# OSO-MISC-20-023_Trinket_SWD_Adapter.net
KiCad netlist of a schematic drawn in EAGLE
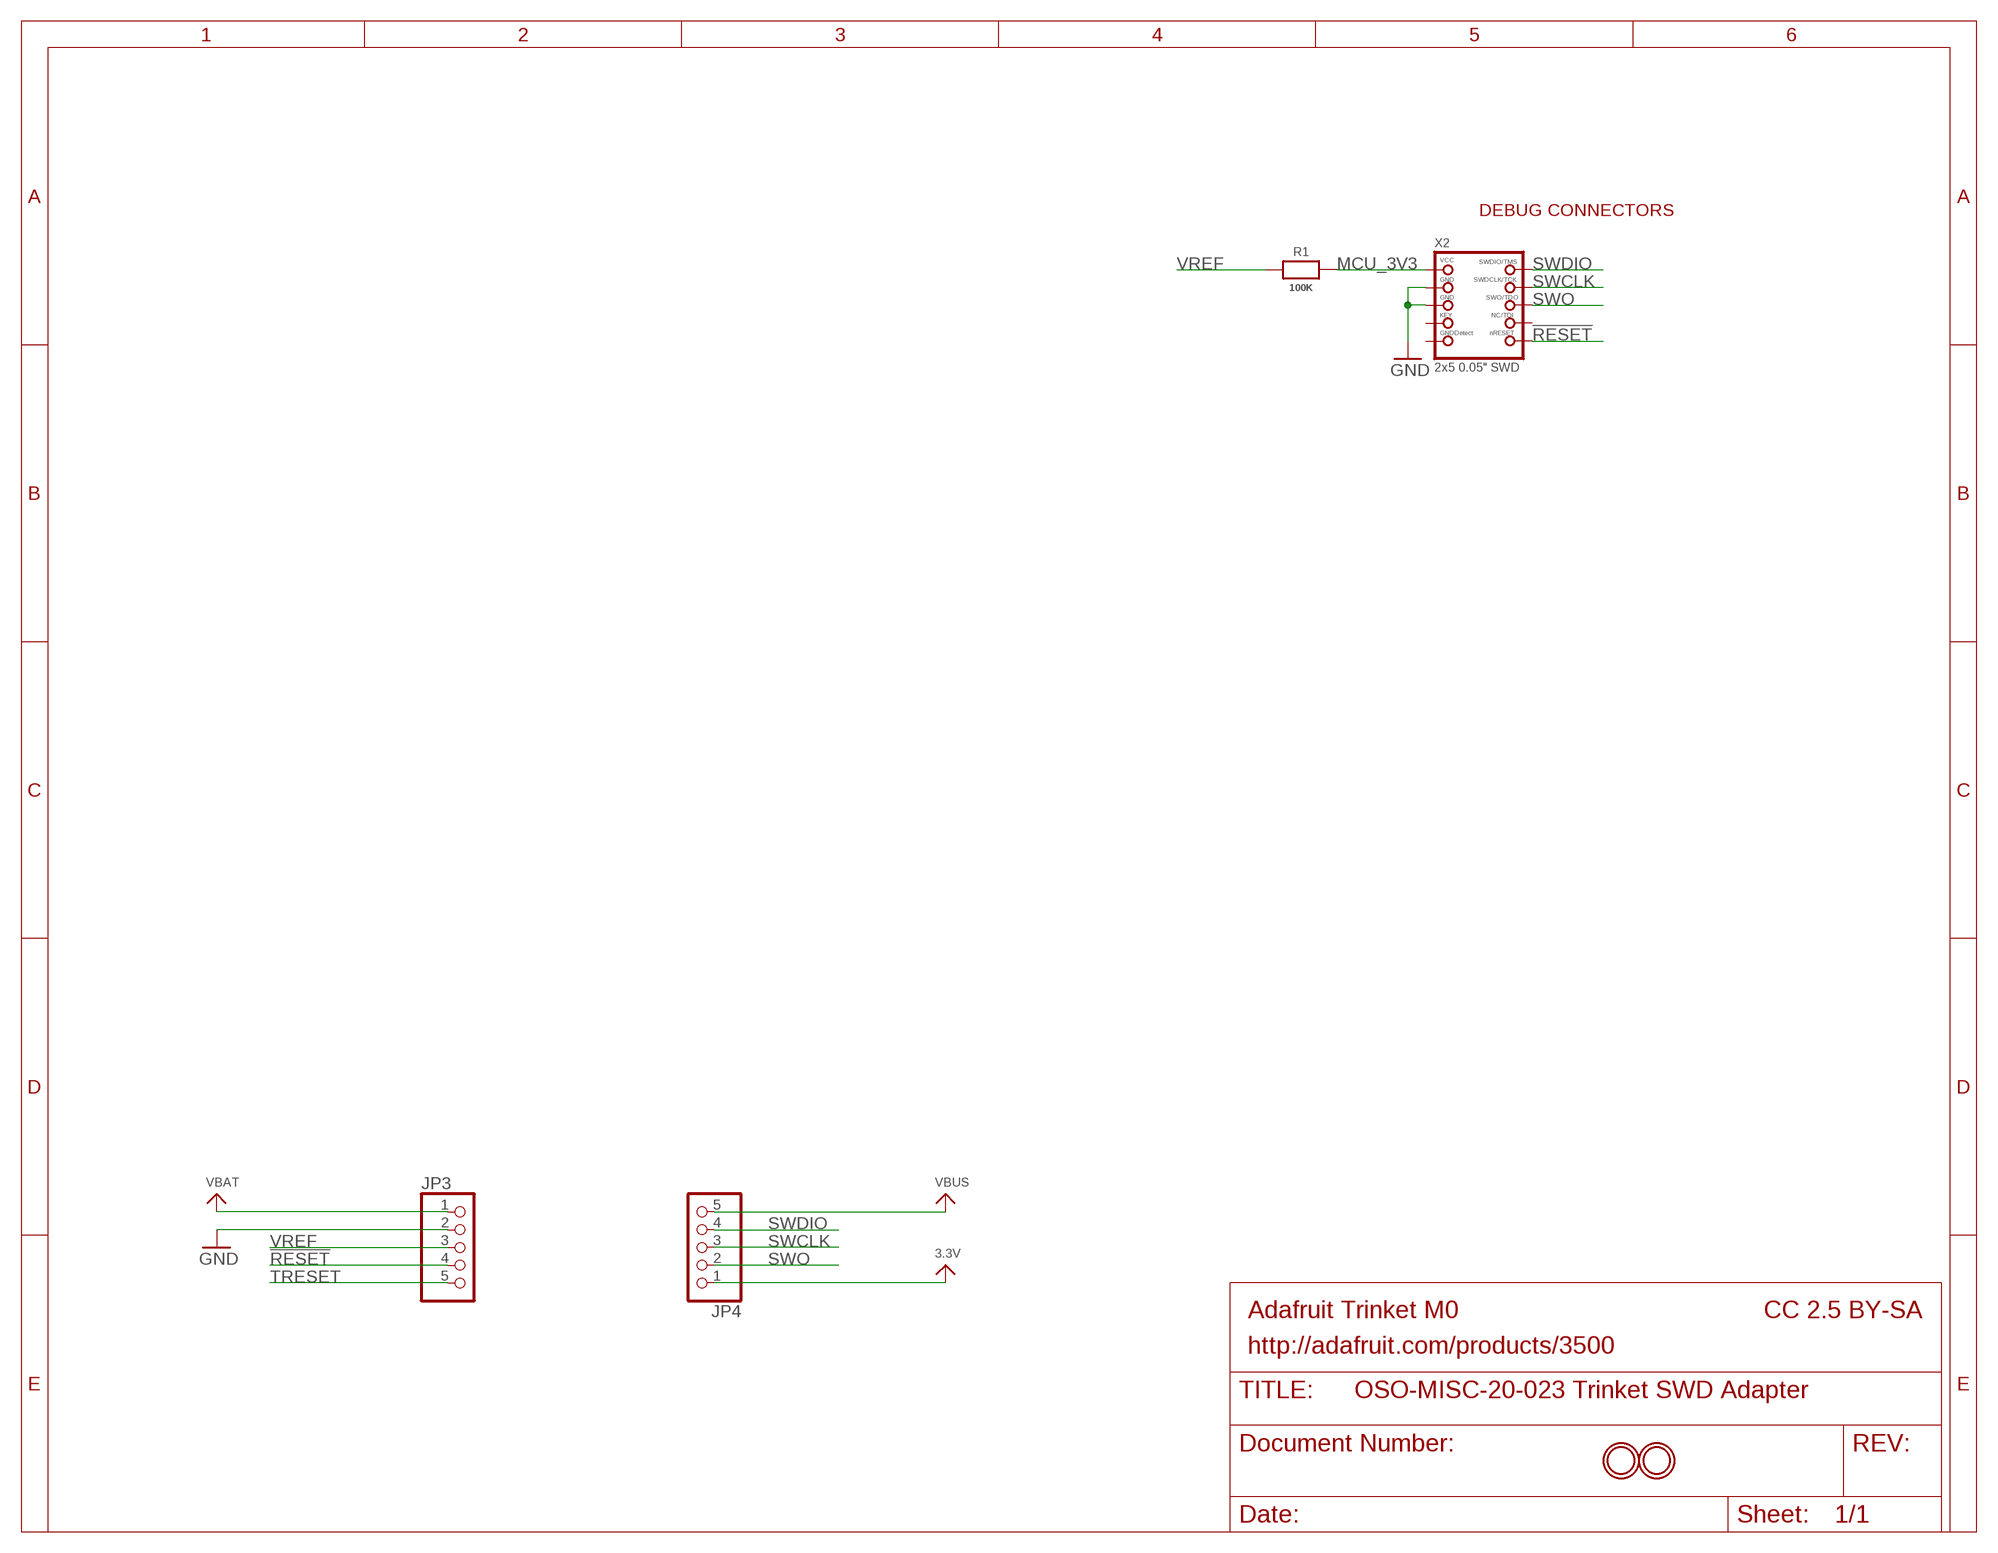
[diagram p0: schematic, sheet 1]

(export (version "E")
  (design (tool "Eeschema 10.0.6"))
  (components
    (comp (ref "JP3")
      (value "HEADER-1X576MIL")
      (footprint "eagle-import:1X05_ROUND_76")
      (libsource (lib "eagle-import") (part "HEADER-1X576MIL"))
    )
    (comp (ref "JP4")
      (value "HEADER-1X576MIL")
      (footprint "eagle-import:1X05_ROUND_76")
      (libsource (lib "eagle-import") (part "HEADER-1X576MIL"))
    )
    (comp (ref "R1")
      (value "100K")
      (footprint "eagle-import:0805-NO")
      (libsource (lib "eagle-import") (part "RESISTOR0805_NOOUTLINE"))
    )
    (comp (ref "U$8")
      (value "MOUNTINGHOLE2.0")
      (footprint "eagle-import:MOUNTINGHOLE_2.0_PLATED")
      (libsource (lib "eagle-import") (part "MOUNTINGHOLE2.0"))
    )
    (comp (ref "U$9")
      (value "MOUNTINGHOLE2.0")
      (footprint "eagle-import:MOUNTINGHOLE_2.0_PLATED")
      (libsource (lib "eagle-import") (part "MOUNTINGHOLE2.0"))
    )
    (comp (ref "X2")
      (value "2x5 0.05\" SWD")
      (footprint "eagle-import:2X05_1.27MM_BOX_POSTS")
      (libsource (lib "eagle-import") (part "JTAG-CORTEXBOXPOSTS"))
    )
  )
  (nets
    (net (code "1") (name "/MCU_3V3") (class "Default")
      (node (ref "R1") (pin "2") (pinfunction "2_2") (pintype "passive"))
      (node (ref "X2") (pin "1") (pinfunction "VCC_1") (pintype "power_in"))
    )
    (net (code "2") (name "/SWCLK") (class "Default")
      (node (ref "JP4") (pin "3") (pinfunction "3_3") (pintype "passive"))
      (node (ref "X2") (pin "4") (pinfunction "SWDCLK_4") (pintype "bidirectional"))
    )
    (net (code "3") (name "/SWDIO") (class "Default")
      (node (ref "JP4") (pin "4") (pinfunction "4_4") (pintype "passive"))
      (node (ref "X2") (pin "2") (pinfunction "SWDIO_2") (pintype "bidirectional"))
    )
    (net (code "4") (name "/SWO") (class "Default")
      (node (ref "JP4") (pin "2") (pinfunction "2_2") (pintype "passive"))
      (node (ref "X2") (pin "6") (pinfunction "SWO_6") (pintype "bidirectional"))
    )
    (net (code "5") (name "/TRESET") (class "Default")
      (node (ref "JP3") (pin "5") (pinfunction "5_5") (pintype "passive"))
    )
    (net (code "6") (name "/VREF") (class "Default")
      (node (ref "JP3") (pin "3") (pinfunction "3_3") (pintype "passive"))
      (node (ref "R1") (pin "1") (pinfunction "1_1") (pintype "passive"))
    )
    (net (code "7") (name "/~{RESET}") (class "Default")
      (node (ref "JP3") (pin "4") (pinfunction "4_4") (pintype "passive"))
      (node (ref "X2") (pin "10") (pinfunction "NRESET_10") (pintype "bidirectional"))
    )
    (net (code "8") (name "3.3V") (class "Default")
      (node (ref "JP4") (pin "1") (pinfunction "1_1") (pintype "passive"))
    )
    (net (code "9") (name "GND") (class "Default")
      (node (ref "JP3") (pin "2") (pinfunction "2_2") (pintype "passive"))
      (node (ref "X2") (pin "3") (pinfunction "GND_3") (pintype "power_in"))
      (node (ref "X2") (pin "5") (pinfunction "GND_5") (pintype "power_in"))
    )
    (net (code "10") (name "VBAT") (class "Default")
      (node (ref "JP3") (pin "1") (pinfunction "1_1") (pintype "passive"))
    )
    (net (code "11") (name "VBUS") (class "Default")
      (node (ref "JP4") (pin "5") (pinfunction "5_5") (pintype "passive"))
    )
    (net (code "12") (name "unconnected-(X2-GNDDETECT-Pad9)") (class "Default")
      (node (ref "X2") (pin "9") (pinfunction "GNDDETECT_9") (pintype "bidirectional"))
    )
    (net (code "13") (name "unconnected-(X2-KEY-Pad7)") (class "Default")
      (node (ref "X2") (pin "7") (pinfunction "KEY_7") (pintype "bidirectional"))
    )
    (net (code "14") (name "unconnected-(X2-TDI-Pad8)") (class "Default")
      (node (ref "X2") (pin "8") (pinfunction "TDI_8") (pintype "bidirectional"))
    )
  )
)
